# W500X.net
KiCad netlist of a schematic drawn in EAGLE
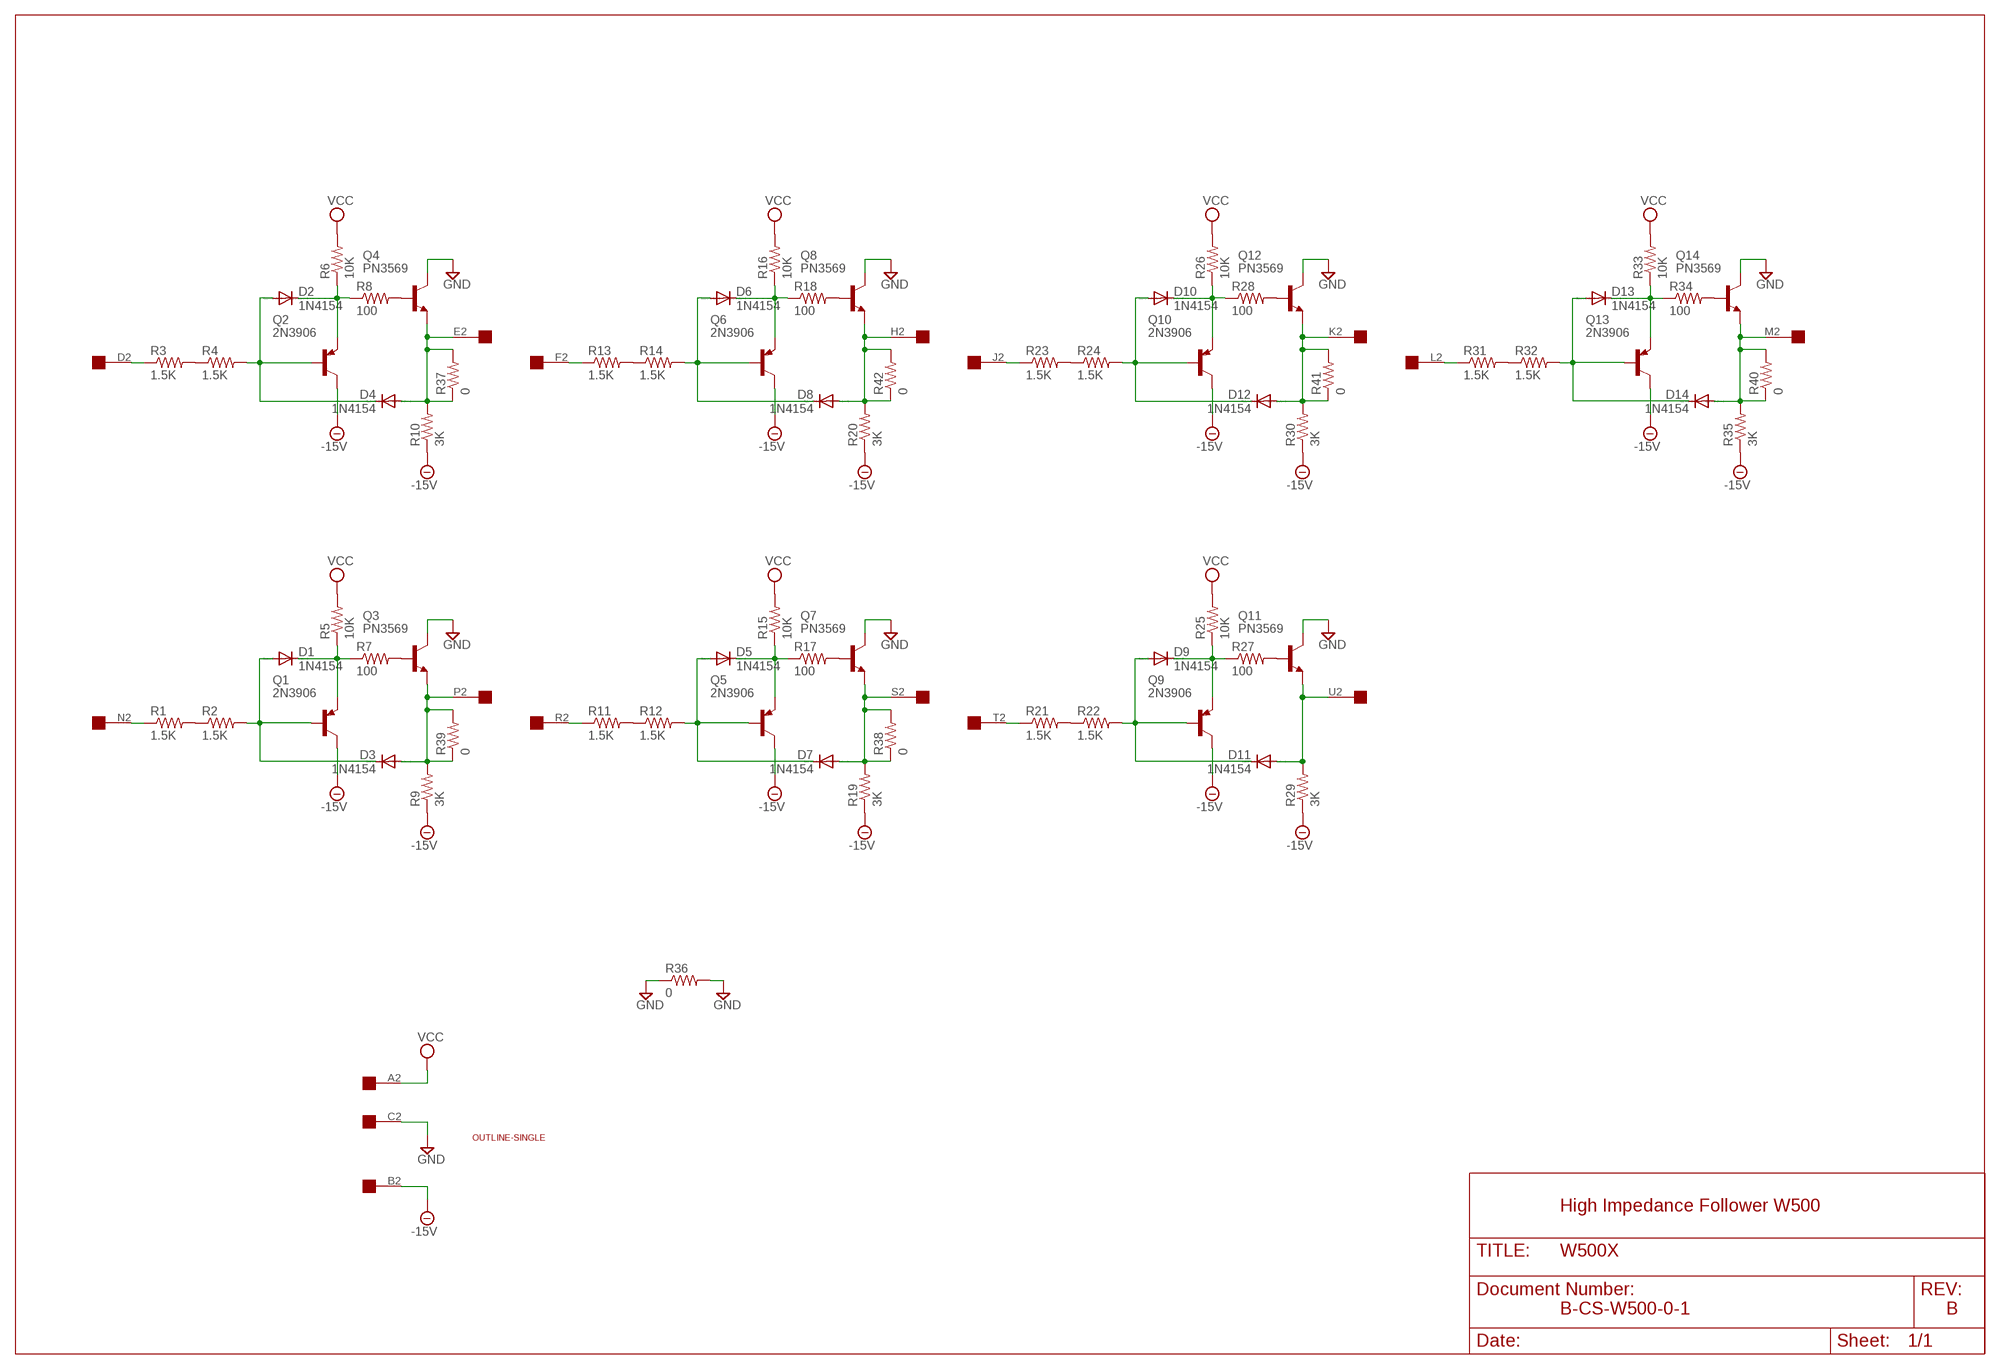
[diagram p0: schematic, sheet 1]

(export (version "E")
  (design (tool "Eeschema 10.0.6"))
  (components
    (comp (ref "D1")
      (value "1N4154")
      (footprint "eagle-import:DO35-10")
      (libsource (lib "eagle-import") (part "DIODE-DO35-10"))
    )
    (comp (ref "D2")
      (value "1N4154")
      (footprint "eagle-import:DO35-10")
      (libsource (lib "eagle-import") (part "DIODE-DO35-10"))
    )
    (comp (ref "D3")
      (value "1N4154")
      (footprint "eagle-import:DO35-10")
      (libsource (lib "eagle-import") (part "DIODE-DO35-10"))
    )
    (comp (ref "D4")
      (value "1N4154")
      (footprint "eagle-import:DO35-10")
      (libsource (lib "eagle-import") (part "DIODE-DO35-10"))
    )
    (comp (ref "D5")
      (value "1N4154")
      (footprint "eagle-import:DO35-10")
      (libsource (lib "eagle-import") (part "DIODE-DO35-10"))
    )
    (comp (ref "D6")
      (value "1N4154")
      (footprint "eagle-import:DO35-10")
      (libsource (lib "eagle-import") (part "DIODE-DO35-10"))
    )
    (comp (ref "D7")
      (value "1N4154")
      (footprint "eagle-import:DO35-10")
      (libsource (lib "eagle-import") (part "DIODE-DO35-10"))
    )
    (comp (ref "D8")
      (value "1N4154")
      (footprint "eagle-import:DO35-10")
      (libsource (lib "eagle-import") (part "DIODE-DO35-10"))
    )
    (comp (ref "D9")
      (value "1N4154")
      (footprint "eagle-import:DO35-10")
      (libsource (lib "eagle-import") (part "DIODE-DO35-10"))
    )
    (comp (ref "D10")
      (value "1N4154")
      (footprint "eagle-import:DO35-10")
      (libsource (lib "eagle-import") (part "DIODE-DO35-10"))
    )
    (comp (ref "D11")
      (value "1N4154")
      (footprint "eagle-import:DO35-10")
      (libsource (lib "eagle-import") (part "DIODE-DO35-10"))
    )
    (comp (ref "D12")
      (value "1N4154")
      (footprint "eagle-import:DO35-10")
      (libsource (lib "eagle-import") (part "DIODE-DO35-10"))
    )
    (comp (ref "D13")
      (value "1N4154")
      (footprint "eagle-import:DO35-10")
      (libsource (lib "eagle-import") (part "DIODE-DO35-10"))
    )
    (comp (ref "D14")
      (value "1N4154")
      (footprint "eagle-import:DO35-10")
      (libsource (lib "eagle-import") (part "DIODE-DO35-10"))
    )
    (comp (ref "Q1")
      (value "2N3906")
      (footprint "eagle-import:TO5")
      (libsource (lib "eagle-import") (part "-PNP-TO5"))
    )
    (comp (ref "Q2")
      (value "2N3906")
      (footprint "eagle-import:TO5")
      (libsource (lib "eagle-import") (part "-PNP-TO5"))
    )
    (comp (ref "Q3")
      (value "PN3569")
      (footprint "eagle-import:TO5")
      (libsource (lib "eagle-import") (part "-NPN-TO5"))
    )
    (comp (ref "Q4")
      (value "PN3569")
      (footprint "eagle-import:TO5")
      (libsource (lib "eagle-import") (part "-NPN-TO5"))
    )
    (comp (ref "Q5")
      (value "2N3906")
      (footprint "eagle-import:TO5")
      (libsource (lib "eagle-import") (part "-PNP-TO5"))
    )
    (comp (ref "Q6")
      (value "2N3906")
      (footprint "eagle-import:TO5")
      (libsource (lib "eagle-import") (part "-PNP-TO5"))
    )
    (comp (ref "Q7")
      (value "PN3569")
      (footprint "eagle-import:TO5")
      (libsource (lib "eagle-import") (part "-NPN-TO5"))
    )
    (comp (ref "Q8")
      (value "PN3569")
      (footprint "eagle-import:TO5")
      (libsource (lib "eagle-import") (part "-NPN-TO5"))
    )
    (comp (ref "Q9")
      (value "2N3906")
      (footprint "eagle-import:TO5")
      (libsource (lib "eagle-import") (part "-PNP-TO5"))
    )
    (comp (ref "Q10")
      (value "2N3906")
      (footprint "eagle-import:TO5")
      (libsource (lib "eagle-import") (part "-PNP-TO5"))
    )
    (comp (ref "Q11")
      (value "PN3569")
      (footprint "eagle-import:TO5")
      (libsource (lib "eagle-import") (part "-NPN-TO5"))
    )
    (comp (ref "Q12")
      (value "PN3569")
      (footprint "eagle-import:TO5")
      (libsource (lib "eagle-import") (part "-NPN-TO5"))
    )
    (comp (ref "Q13")
      (value "2N3906")
      (footprint "eagle-import:TO5")
      (libsource (lib "eagle-import") (part "-PNP-TO5"))
    )
    (comp (ref "Q14")
      (value "PN3569")
      (footprint "eagle-import:TO5")
      (libsource (lib "eagle-import") (part "-NPN-TO5"))
    )
    (comp (ref "R1")
      (value "1.5K")
      (footprint "eagle-import:0207_10")
      (libsource (lib "eagle-import") (part "R-US_0207/10"))
    )
    (comp (ref "R2")
      (value "1.5K")
      (footprint "eagle-import:0207_10")
      (libsource (lib "eagle-import") (part "R-US_0207/10"))
    )
    (comp (ref "R3")
      (value "1.5K")
      (footprint "eagle-import:0207_10")
      (libsource (lib "eagle-import") (part "R-US_0207/10"))
    )
    (comp (ref "R4")
      (value "1.5K")
      (footprint "eagle-import:0207_10")
      (libsource (lib "eagle-import") (part "R-US_0207/10"))
    )
    (comp (ref "R5")
      (value "10K")
      (footprint "eagle-import:0207_10")
      (libsource (lib "eagle-import") (part "R-US_0207/10"))
    )
    (comp (ref "R6")
      (value "10K")
      (footprint "eagle-import:0207_10")
      (libsource (lib "eagle-import") (part "R-US_0207/10"))
    )
    (comp (ref "R7")
      (value "100")
      (footprint "eagle-import:0207_10")
      (libsource (lib "eagle-import") (part "R-US_0207/10"))
    )
    (comp (ref "R8")
      (value "100")
      (footprint "eagle-import:0207_10")
      (libsource (lib "eagle-import") (part "R-US_0207/10"))
    )
    (comp (ref "R9")
      (value "3K")
      (footprint "eagle-import:0207_10")
      (libsource (lib "eagle-import") (part "R-US_0207/10"))
    )
    (comp (ref "R10")
      (value "3K")
      (footprint "eagle-import:0207_10")
      (libsource (lib "eagle-import") (part "R-US_0207/10"))
    )
    (comp (ref "R11")
      (value "1.5K")
      (footprint "eagle-import:0207_10")
      (libsource (lib "eagle-import") (part "R-US_0207/10"))
    )
    (comp (ref "R12")
      (value "1.5K")
      (footprint "eagle-import:0207_10")
      (libsource (lib "eagle-import") (part "R-US_0207/10"))
    )
    (comp (ref "R13")
      (value "1.5K")
      (footprint "eagle-import:0207_10")
      (libsource (lib "eagle-import") (part "R-US_0207/10"))
    )
    (comp (ref "R14")
      (value "1.5K")
      (footprint "eagle-import:0207_10")
      (libsource (lib "eagle-import") (part "R-US_0207/10"))
    )
    (comp (ref "R15")
      (value "10K")
      (footprint "eagle-import:0207_10")
      (libsource (lib "eagle-import") (part "R-US_0207/10"))
    )
    (comp (ref "R16")
      (value "10K")
      (footprint "eagle-import:0207_10")
      (libsource (lib "eagle-import") (part "R-US_0207/10"))
    )
    (comp (ref "R17")
      (value "100")
      (footprint "eagle-import:0207_10")
      (libsource (lib "eagle-import") (part "R-US_0207/10"))
    )
    (comp (ref "R18")
      (value "100")
      (footprint "eagle-import:0207_10")
      (libsource (lib "eagle-import") (part "R-US_0207/10"))
    )
    (comp (ref "R19")
      (value "3K")
      (footprint "eagle-import:0207_10")
      (libsource (lib "eagle-import") (part "R-US_0207/10"))
    )
    (comp (ref "R20")
      (value "3K")
      (footprint "eagle-import:0207_10")
      (libsource (lib "eagle-import") (part "R-US_0207/10"))
    )
    (comp (ref "R21")
      (value "1.5K")
      (footprint "eagle-import:0207_10")
      (libsource (lib "eagle-import") (part "R-US_0207/10"))
    )
    (comp (ref "R22")
      (value "1.5K")
      (footprint "eagle-import:0207_10")
      (libsource (lib "eagle-import") (part "R-US_0207/10"))
    )
    (comp (ref "R23")
      (value "1.5K")
      (footprint "eagle-import:0207_10")
      (libsource (lib "eagle-import") (part "R-US_0207/10"))
    )
    (comp (ref "R24")
      (value "1.5K")
      (footprint "eagle-import:0207_10")
      (libsource (lib "eagle-import") (part "R-US_0207/10"))
    )
    (comp (ref "R25")
      (value "10K")
      (footprint "eagle-import:0207_10")
      (libsource (lib "eagle-import") (part "R-US_0207/10"))
    )
    (comp (ref "R26")
      (value "10K")
      (footprint "eagle-import:0207_10")
      (libsource (lib "eagle-import") (part "R-US_0207/10"))
    )
    (comp (ref "R27")
      (value "100")
      (footprint "eagle-import:0207_10")
      (libsource (lib "eagle-import") (part "R-US_0207/10"))
    )
    (comp (ref "R28")
      (value "100")
      (footprint "eagle-import:0207_10")
      (libsource (lib "eagle-import") (part "R-US_0207/10"))
    )
    (comp (ref "R29")
      (value "3K")
      (footprint "eagle-import:0207_10")
      (libsource (lib "eagle-import") (part "R-US_0207/10"))
    )
    (comp (ref "R30")
      (value "3K")
      (footprint "eagle-import:0207_10")
      (libsource (lib "eagle-import") (part "R-US_0207/10"))
    )
    (comp (ref "R31")
      (value "1.5K")
      (footprint "eagle-import:0207_10")
      (libsource (lib "eagle-import") (part "R-US_0207/10"))
    )
    (comp (ref "R32")
      (value "1.5K")
      (footprint "eagle-import:0207_10")
      (libsource (lib "eagle-import") (part "R-US_0207/10"))
    )
    (comp (ref "R33")
      (value "10K")
      (footprint "eagle-import:0207_10")
      (libsource (lib "eagle-import") (part "R-US_0207/10"))
    )
    (comp (ref "R34")
      (value "100")
      (footprint "eagle-import:0207_10")
      (libsource (lib "eagle-import") (part "R-US_0207/10"))
    )
    (comp (ref "R35")
      (value "3K")
      (footprint "eagle-import:0207_10")
      (libsource (lib "eagle-import") (part "R-US_0207/10"))
    )
    (comp (ref "R36")
      (value "0")
      (footprint "eagle-import:0207_10")
      (libsource (lib "eagle-import") (part "R-US_0207/10"))
    )
    (comp (ref "R37")
      (value "0")
      (footprint "eagle-import:0207_10")
      (libsource (lib "eagle-import") (part "R-US_0207/10"))
    )
    (comp (ref "R38")
      (value "0")
      (footprint "eagle-import:0207_10")
      (libsource (lib "eagle-import") (part "R-US_0207/10"))
    )
    (comp (ref "R39")
      (value "0")
      (footprint "eagle-import:0207_10")
      (libsource (lib "eagle-import") (part "R-US_0207/10"))
    )
    (comp (ref "R40")
      (value "0")
      (footprint "eagle-import:0207_10")
      (libsource (lib "eagle-import") (part "R-US_0207/10"))
    )
    (comp (ref "R41")
      (value "0")
      (footprint "eagle-import:0207_10")
      (libsource (lib "eagle-import") (part "R-US_0207/10"))
    )
    (comp (ref "R42")
      (value "0")
      (footprint "eagle-import:0207_10")
      (libsource (lib "eagle-import") (part "R-US_0207/10"))
    )
    (comp (ref "U$1")
      (value "OUTLINE-SINGLE")
      (footprint "eagle-import:SINGLE")
      (libsource (lib "eagle-import") (part "OUTLINE-SINGLE"))
    )
    (comp (ref "U$2")
      (value "EDGE-1")
      (footprint "eagle-import:EDGE-CON1")
      (libsource (lib "eagle-import") (part "EDGE-1"))
    )
  )
  (nets
    (net (code "1") (name "-15V") (class "Default")
      (node (ref "Q1") (pin "3") (pinfunction "C_3") (pintype "passive"))
      (node (ref "Q10") (pin "3") (pinfunction "C_3") (pintype "passive"))
      (node (ref "Q13") (pin "3") (pinfunction "C_3") (pintype "passive"))
      (node (ref "Q2") (pin "3") (pinfunction "C_3") (pintype "passive"))
      (node (ref "Q5") (pin "3") (pinfunction "C_3") (pintype "passive"))
      (node (ref "Q6") (pin "3") (pinfunction "C_3") (pintype "passive"))
      (node (ref "Q9") (pin "3") (pinfunction "C_3") (pintype "passive"))
      (node (ref "R10") (pin "1") (pinfunction "1_1") (pintype "passive"))
      (node (ref "R19") (pin "1") (pinfunction "1_1") (pintype "passive"))
      (node (ref "R20") (pin "1") (pinfunction "1_1") (pintype "passive"))
      (node (ref "R29") (pin "1") (pinfunction "1_1") (pintype "passive"))
      (node (ref "R30") (pin "1") (pinfunction "1_1") (pintype "passive"))
      (node (ref "R35") (pin "1") (pinfunction "1_1") (pintype "passive"))
      (node (ref "R9") (pin "1") (pinfunction "1_1") (pintype "passive"))
      (node (ref "U$2") (pin "B2") (pinfunction "1_B2") (pintype "bidirectional"))
    )
    (net (code "2") (name "GND") (class "Default")
      (node (ref "Q11") (pin "3") (pinfunction "C_3") (pintype "passive"))
      (node (ref "Q12") (pin "3") (pinfunction "C_3") (pintype "passive"))
      (node (ref "Q14") (pin "3") (pinfunction "C_3") (pintype "passive"))
      (node (ref "Q3") (pin "3") (pinfunction "C_3") (pintype "passive"))
      (node (ref "Q4") (pin "3") (pinfunction "C_3") (pintype "passive"))
      (node (ref "Q7") (pin "3") (pinfunction "C_3") (pintype "passive"))
      (node (ref "Q8") (pin "3") (pinfunction "C_3") (pintype "passive"))
      (node (ref "R36") (pin "1") (pinfunction "1_1") (pintype "passive"))
      (node (ref "R36") (pin "2") (pinfunction "2_2") (pintype "passive"))
      (node (ref "U$2") (pin "C2") (pinfunction "1_C2") (pintype "bidirectional"))
    )
    (net (code "3") (name "Net-(Q1-B)") (class "Default")
      (node (ref "D1") (pin "A") (pinfunction "A_A") (pintype "passive"))
      (node (ref "D3") (pin "C") (pinfunction "C_C") (pintype "passive"))
      (node (ref "Q1") (pin "2") (pinfunction "B_2") (pintype "passive"))
      (node (ref "R2") (pin "2") (pinfunction "2_2") (pintype "passive"))
    )
    (net (code "4") (name "Net-(Q1-E)") (class "Default")
      (node (ref "D1") (pin "C") (pinfunction "C_C") (pintype "passive"))
      (node (ref "Q1") (pin "1") (pinfunction "E_1") (pintype "passive"))
      (node (ref "R5") (pin "1") (pinfunction "1_1") (pintype "passive"))
      (node (ref "R7") (pin "1") (pinfunction "1_1") (pintype "passive"))
    )
    (net (code "5") (name "Net-(Q2-B)") (class "Default")
      (node (ref "D2") (pin "A") (pinfunction "A_A") (pintype "passive"))
      (node (ref "D4") (pin "C") (pinfunction "C_C") (pintype "passive"))
      (node (ref "Q2") (pin "2") (pinfunction "B_2") (pintype "passive"))
      (node (ref "R4") (pin "2") (pinfunction "2_2") (pintype "passive"))
    )
    (net (code "6") (name "Net-(Q2-E)") (class "Default")
      (node (ref "D2") (pin "C") (pinfunction "C_C") (pintype "passive"))
      (node (ref "Q2") (pin "1") (pinfunction "E_1") (pintype "passive"))
      (node (ref "R6") (pin "1") (pinfunction "1_1") (pintype "passive"))
      (node (ref "R8") (pin "1") (pinfunction "1_1") (pintype "passive"))
    )
    (net (code "7") (name "Net-(Q3-B)") (class "Default")
      (node (ref "Q3") (pin "2") (pinfunction "B_2") (pintype "passive"))
      (node (ref "R7") (pin "2") (pinfunction "2_2") (pintype "passive"))
    )
    (net (code "8") (name "Net-(Q3-E)") (class "Default")
      (node (ref "D3") (pin "A") (pinfunction "A_A") (pintype "passive"))
      (node (ref "Q3") (pin "1") (pinfunction "E_1") (pintype "passive"))
      (node (ref "R39") (pin "1") (pinfunction "1_1") (pintype "passive"))
      (node (ref "R39") (pin "2") (pinfunction "2_2") (pintype "passive"))
      (node (ref "R9") (pin "2") (pinfunction "2_2") (pintype "passive"))
      (node (ref "U$2") (pin "P2") (pinfunction "1_P2") (pintype "bidirectional"))
    )
    (net (code "9") (name "Net-(Q4-B)") (class "Default")
      (node (ref "Q4") (pin "2") (pinfunction "B_2") (pintype "passive"))
      (node (ref "R8") (pin "2") (pinfunction "2_2") (pintype "passive"))
    )
    (net (code "10") (name "Net-(Q4-E)") (class "Default")
      (node (ref "D4") (pin "A") (pinfunction "A_A") (pintype "passive"))
      (node (ref "Q4") (pin "1") (pinfunction "E_1") (pintype "passive"))
      (node (ref "R10") (pin "2") (pinfunction "2_2") (pintype "passive"))
      (node (ref "R37") (pin "1") (pinfunction "1_1") (pintype "passive"))
      (node (ref "R37") (pin "2") (pinfunction "2_2") (pintype "passive"))
      (node (ref "U$2") (pin "E2") (pinfunction "1_E2") (pintype "bidirectional"))
    )
    (net (code "11") (name "Net-(Q5-B)") (class "Default")
      (node (ref "D5") (pin "A") (pinfunction "A_A") (pintype "passive"))
      (node (ref "D7") (pin "C") (pinfunction "C_C") (pintype "passive"))
      (node (ref "Q5") (pin "2") (pinfunction "B_2") (pintype "passive"))
      (node (ref "R12") (pin "2") (pinfunction "2_2") (pintype "passive"))
    )
    (net (code "12") (name "Net-(Q5-E)") (class "Default")
      (node (ref "D5") (pin "C") (pinfunction "C_C") (pintype "passive"))
      (node (ref "Q5") (pin "1") (pinfunction "E_1") (pintype "passive"))
      (node (ref "R15") (pin "1") (pinfunction "1_1") (pintype "passive"))
      (node (ref "R17") (pin "1") (pinfunction "1_1") (pintype "passive"))
    )
    (net (code "13") (name "Net-(Q6-B)") (class "Default")
      (node (ref "D6") (pin "A") (pinfunction "A_A") (pintype "passive"))
      (node (ref "D8") (pin "C") (pinfunction "C_C") (pintype "passive"))
      (node (ref "Q6") (pin "2") (pinfunction "B_2") (pintype "passive"))
      (node (ref "R14") (pin "2") (pinfunction "2_2") (pintype "passive"))
    )
    (net (code "14") (name "Net-(Q6-E)") (class "Default")
      (node (ref "D6") (pin "C") (pinfunction "C_C") (pintype "passive"))
      (node (ref "Q6") (pin "1") (pinfunction "E_1") (pintype "passive"))
      (node (ref "R16") (pin "1") (pinfunction "1_1") (pintype "passive"))
      (node (ref "R18") (pin "1") (pinfunction "1_1") (pintype "passive"))
    )
    (net (code "15") (name "Net-(Q7-B)") (class "Default")
      (node (ref "Q7") (pin "2") (pinfunction "B_2") (pintype "passive"))
      (node (ref "R17") (pin "2") (pinfunction "2_2") (pintype "passive"))
    )
    (net (code "16") (name "Net-(Q7-E)") (class "Default")
      (node (ref "D7") (pin "A") (pinfunction "A_A") (pintype "passive"))
      (node (ref "Q7") (pin "1") (pinfunction "E_1") (pintype "passive"))
      (node (ref "R19") (pin "2") (pinfunction "2_2") (pintype "passive"))
      (node (ref "R38") (pin "1") (pinfunction "1_1") (pintype "passive"))
      (node (ref "R38") (pin "2") (pinfunction "2_2") (pintype "passive"))
      (node (ref "U$2") (pin "S2") (pinfunction "1_S2") (pintype "bidirectional"))
    )
    (net (code "17") (name "Net-(Q8-B)") (class "Default")
      (node (ref "Q8") (pin "2") (pinfunction "B_2") (pintype "passive"))
      (node (ref "R18") (pin "2") (pinfunction "2_2") (pintype "passive"))
    )
    (net (code "18") (name "Net-(Q8-E)") (class "Default")
      (node (ref "D8") (pin "A") (pinfunction "A_A") (pintype "passive"))
      (node (ref "Q8") (pin "1") (pinfunction "E_1") (pintype "passive"))
      (node (ref "R20") (pin "2") (pinfunction "2_2") (pintype "passive"))
      (node (ref "R42") (pin "1") (pinfunction "1_1") (pintype "passive"))
      (node (ref "R42") (pin "2") (pinfunction "2_2") (pintype "passive"))
      (node (ref "U$2") (pin "H2") (pinfunction "1_H2") (pintype "bidirectional"))
    )
    (net (code "19") (name "Net-(Q9-B)") (class "Default")
      (node (ref "D11") (pin "C") (pinfunction "C_C") (pintype "passive"))
      (node (ref "D9") (pin "A") (pinfunction "A_A") (pintype "passive"))
      (node (ref "Q9") (pin "2") (pinfunction "B_2") (pintype "passive"))
      (node (ref "R22") (pin "2") (pinfunction "2_2") (pintype "passive"))
    )
    (net (code "20") (name "Net-(Q9-E)") (class "Default")
      (node (ref "D9") (pin "C") (pinfunction "C_C") (pintype "passive"))
      (node (ref "Q9") (pin "1") (pinfunction "E_1") (pintype "passive"))
      (node (ref "R25") (pin "1") (pinfunction "1_1") (pintype "passive"))
      (node (ref "R27") (pin "1") (pinfunction "1_1") (pintype "passive"))
    )
    (net (code "21") (name "Net-(Q10-B)") (class "Default")
      (node (ref "D10") (pin "A") (pinfunction "A_A") (pintype "passive"))
      (node (ref "D12") (pin "C") (pinfunction "C_C") (pintype "passive"))
      (node (ref "Q10") (pin "2") (pinfunction "B_2") (pintype "passive"))
      (node (ref "R24") (pin "2") (pinfunction "2_2") (pintype "passive"))
    )
    (net (code "22") (name "Net-(Q10-E)") (class "Default")
      (node (ref "D10") (pin "C") (pinfunction "C_C") (pintype "passive"))
      (node (ref "Q10") (pin "1") (pinfunction "E_1") (pintype "passive"))
      (node (ref "R26") (pin "1") (pinfunction "1_1") (pintype "passive"))
      (node (ref "R28") (pin "1") (pinfunction "1_1") (pintype "passive"))
    )
    (net (code "23") (name "Net-(Q11-B)") (class "Default")
      (node (ref "Q11") (pin "2") (pinfunction "B_2") (pintype "passive"))
      (node (ref "R27") (pin "2") (pinfunction "2_2") (pintype "passive"))
    )
    (net (code "24") (name "Net-(Q11-E)") (class "Default")
      (node (ref "D11") (pin "A") (pinfunction "A_A") (pintype "passive"))
      (node (ref "Q11") (pin "1") (pinfunction "E_1") (pintype "passive"))
      (node (ref "R29") (pin "2") (pinfunction "2_2") (pintype "passive"))
      (node (ref "U$2") (pin "U2") (pinfunction "1_U2") (pintype "bidirectional"))
    )
    (net (code "25") (name "Net-(Q12-B)") (class "Default")
      (node (ref "Q12") (pin "2") (pinfunction "B_2") (pintype "passive"))
      (node (ref "R28") (pin "2") (pinfunction "2_2") (pintype "passive"))
    )
    (net (code "26") (name "Net-(Q12-E)") (class "Default")
      (node (ref "D12") (pin "A") (pinfunction "A_A") (pintype "passive"))
      (node (ref "Q12") (pin "1") (pinfunction "E_1") (pintype "passive"))
      (node (ref "R30") (pin "2") (pinfunction "2_2") (pintype "passive"))
      (node (ref "R41") (pin "1") (pinfunction "1_1") (pintype "passive"))
      (node (ref "R41") (pin "2") (pinfunction "2_2") (pintype "passive"))
      (node (ref "U$2") (pin "K2") (pinfunction "1_K2") (pintype "bidirectional"))
    )
    (net (code "27") (name "Net-(Q13-B)") (class "Default")
      (node (ref "D13") (pin "A") (pinfunction "A_A") (pintype "passive"))
      (node (ref "D14") (pin "C") (pinfunction "C_C") (pintype "passive"))
      (node (ref "Q13") (pin "2") (pinfunction "B_2") (pintype "passive"))
      (node (ref "R32") (pin "2") (pinfunction "2_2") (pintype "passive"))
    )
    (net (code "28") (name "Net-(Q13-E)") (class "Default")
      (node (ref "D13") (pin "C") (pinfunction "C_C") (pintype "passive"))
      (node (ref "Q13") (pin "1") (pinfunction "E_1") (pintype "passive"))
      (node (ref "R33") (pin "1") (pinfunction "1_1") (pintype "passive"))
      (node (ref "R34") (pin "1") (pinfunction "1_1") (pintype "passive"))
    )
    (net (code "29") (name "Net-(Q14-B)") (class "Default")
      (node (ref "Q14") (pin "2") (pinfunction "B_2") (pintype "passive"))
      (node (ref "R34") (pin "2") (pinfunction "2_2") (pintype "passive"))
    )
    (net (code "30") (name "Net-(Q14-E)") (class "Default")
      (node (ref "D14") (pin "A") (pinfunction "A_A") (pintype "passive"))
      (node (ref "Q14") (pin "1") (pinfunction "E_1") (pintype "passive"))
      (node (ref "R35") (pin "2") (pinfunction "2_2") (pintype "passive"))
      (node (ref "R40") (pin "1") (pinfunction "1_1") (pintype "passive"))
      (node (ref "R40") (pin "2") (pinfunction "2_2") (pintype "passive"))
      (node (ref "U$2") (pin "M2") (pinfunction "1_M2") (pintype "bidirectional"))
    )
    (net (code "31") (name "Net-(R1-Pad2)") (class "Default")
      (node (ref "R1") (pin "2") (pinfunction "2_2") (pintype "passive"))
      (node (ref "R2") (pin "1") (pinfunction "1_1") (pintype "passive"))
    )
    (net (code "32") (name "Net-(R3-Pad2)") (class "Default")
      (node (ref "R3") (pin "2") (pinfunction "2_2") (pintype "passive"))
      (node (ref "R4") (pin "1") (pinfunction "1_1") (pintype "passive"))
    )
    (net (code "33") (name "Net-(R11-Pad2)") (class "Default")
      (node (ref "R11") (pin "2") (pinfunction "2_2") (pintype "passive"))
      (node (ref "R12") (pin "1") (pinfunction "1_1") (pintype "passive"))
    )
    (net (code "34") (name "Net-(R13-Pad2)") (class "Default")
      (node (ref "R13") (pin "2") (pinfunction "2_2") (pintype "passive"))
      (node (ref "R14") (pin "1") (pinfunction "1_1") (pintype "passive"))
    )
    (net (code "35") (name "Net-(R21-Pad2)") (class "Default")
      (node (ref "R21") (pin "2") (pinfunction "2_2") (pintype "passive"))
      (node (ref "R22") (pin "1") (pinfunction "1_1") (pintype "passive"))
    )
    (net (code "36") (name "Net-(R23-Pad2)") (class "Default")
      (node (ref "R23") (pin "2") (pinfunction "2_2") (pintype "passive"))
      (node (ref "R24") (pin "1") (pinfunction "1_1") (pintype "passive"))
    )
    (net (code "37") (name "Net-(R31-Pad2)") (class "Default")
      (node (ref "R31") (pin "2") (pinfunction "2_2") (pintype "passive"))
      (node (ref "R32") (pin "1") (pinfunction "1_1") (pintype "passive"))
    )
    (net (code "38") (name "Net-(U$2D-1)") (class "Default")
      (node (ref "R3") (pin "1") (pinfunction "1_1") (pintype "passive"))
      (node (ref "U$2") (pin "D2") (pinfunction "1_D2") (pintype "bidirectional"))
    )
    (net (code "39") (name "Net-(U$2F-1)") (class "Default")
      (node (ref "R13") (pin "1") (pinfunction "1_1") (pintype "passive"))
      (node (ref "U$2") (pin "F2") (pinfunction "1_F2") (pintype "bidirectional"))
    )
    (net (code "40") (name "Net-(U$2H-1)") (class "Default")
      (node (ref "R23") (pin "1") (pinfunction "1_1") (pintype "passive"))
      (node (ref "U$2") (pin "J2") (pinfunction "1_J2") (pintype "bidirectional"))
    )
    (net (code "41") (name "Net-(U$2J-1)") (class "Default")
      (node (ref "R31") (pin "1") (pinfunction "1_1") (pintype "passive"))
      (node (ref "U$2") (pin "L2") (pinfunction "1_L2") (pintype "bidirectional"))
    )
    (net (code "42") (name "Net-(U$2L-1)") (class "Default")
      (node (ref "R1") (pin "1") (pinfunction "1_1") (pintype "passive"))
      (node (ref "U$2") (pin "N2") (pinfunction "1_N2") (pintype "bidirectional"))
    )
    (net (code "43") (name "Net-(U$2N-1)") (class "Default")
      (node (ref "R11") (pin "1") (pinfunction "1_1") (pintype "passive"))
      (node (ref "U$2") (pin "R2") (pinfunction "1_R2") (pintype "bidirectional"))
    )
    (net (code "44") (name "Net-(U$2P-1)") (class "Default")
      (node (ref "R21") (pin "1") (pinfunction "1_1") (pintype "passive"))
      (node (ref "U$2") (pin "T2") (pinfunction "1_T2") (pintype "bidirectional"))
    )
    (net (code "45") (name "VCC") (class "Default")
      (node (ref "R15") (pin "2") (pinfunction "2_2") (pintype "passive"))
      (node (ref "R16") (pin "2") (pinfunction "2_2") (pintype "passive"))
      (node (ref "R25") (pin "2") (pinfunction "2_2") (pintype "passive"))
      (node (ref "R26") (pin "2") (pinfunction "2_2") (pintype "passive"))
      (node (ref "R33") (pin "2") (pinfunction "2_2") (pintype "passive"))
      (node (ref "R5") (pin "2") (pinfunction "2_2") (pintype "passive"))
      (node (ref "R6") (pin "2") (pinfunction "2_2") (pintype "passive"))
      (node (ref "U$2") (pin "A2") (pinfunction "1_A2") (pintype "bidirectional"))
    )
  )
)
